# ProPrj_LED__2025-12-14-09-56-37.net
KiCad netlist of a schematic drawn in EasyEDA Pro
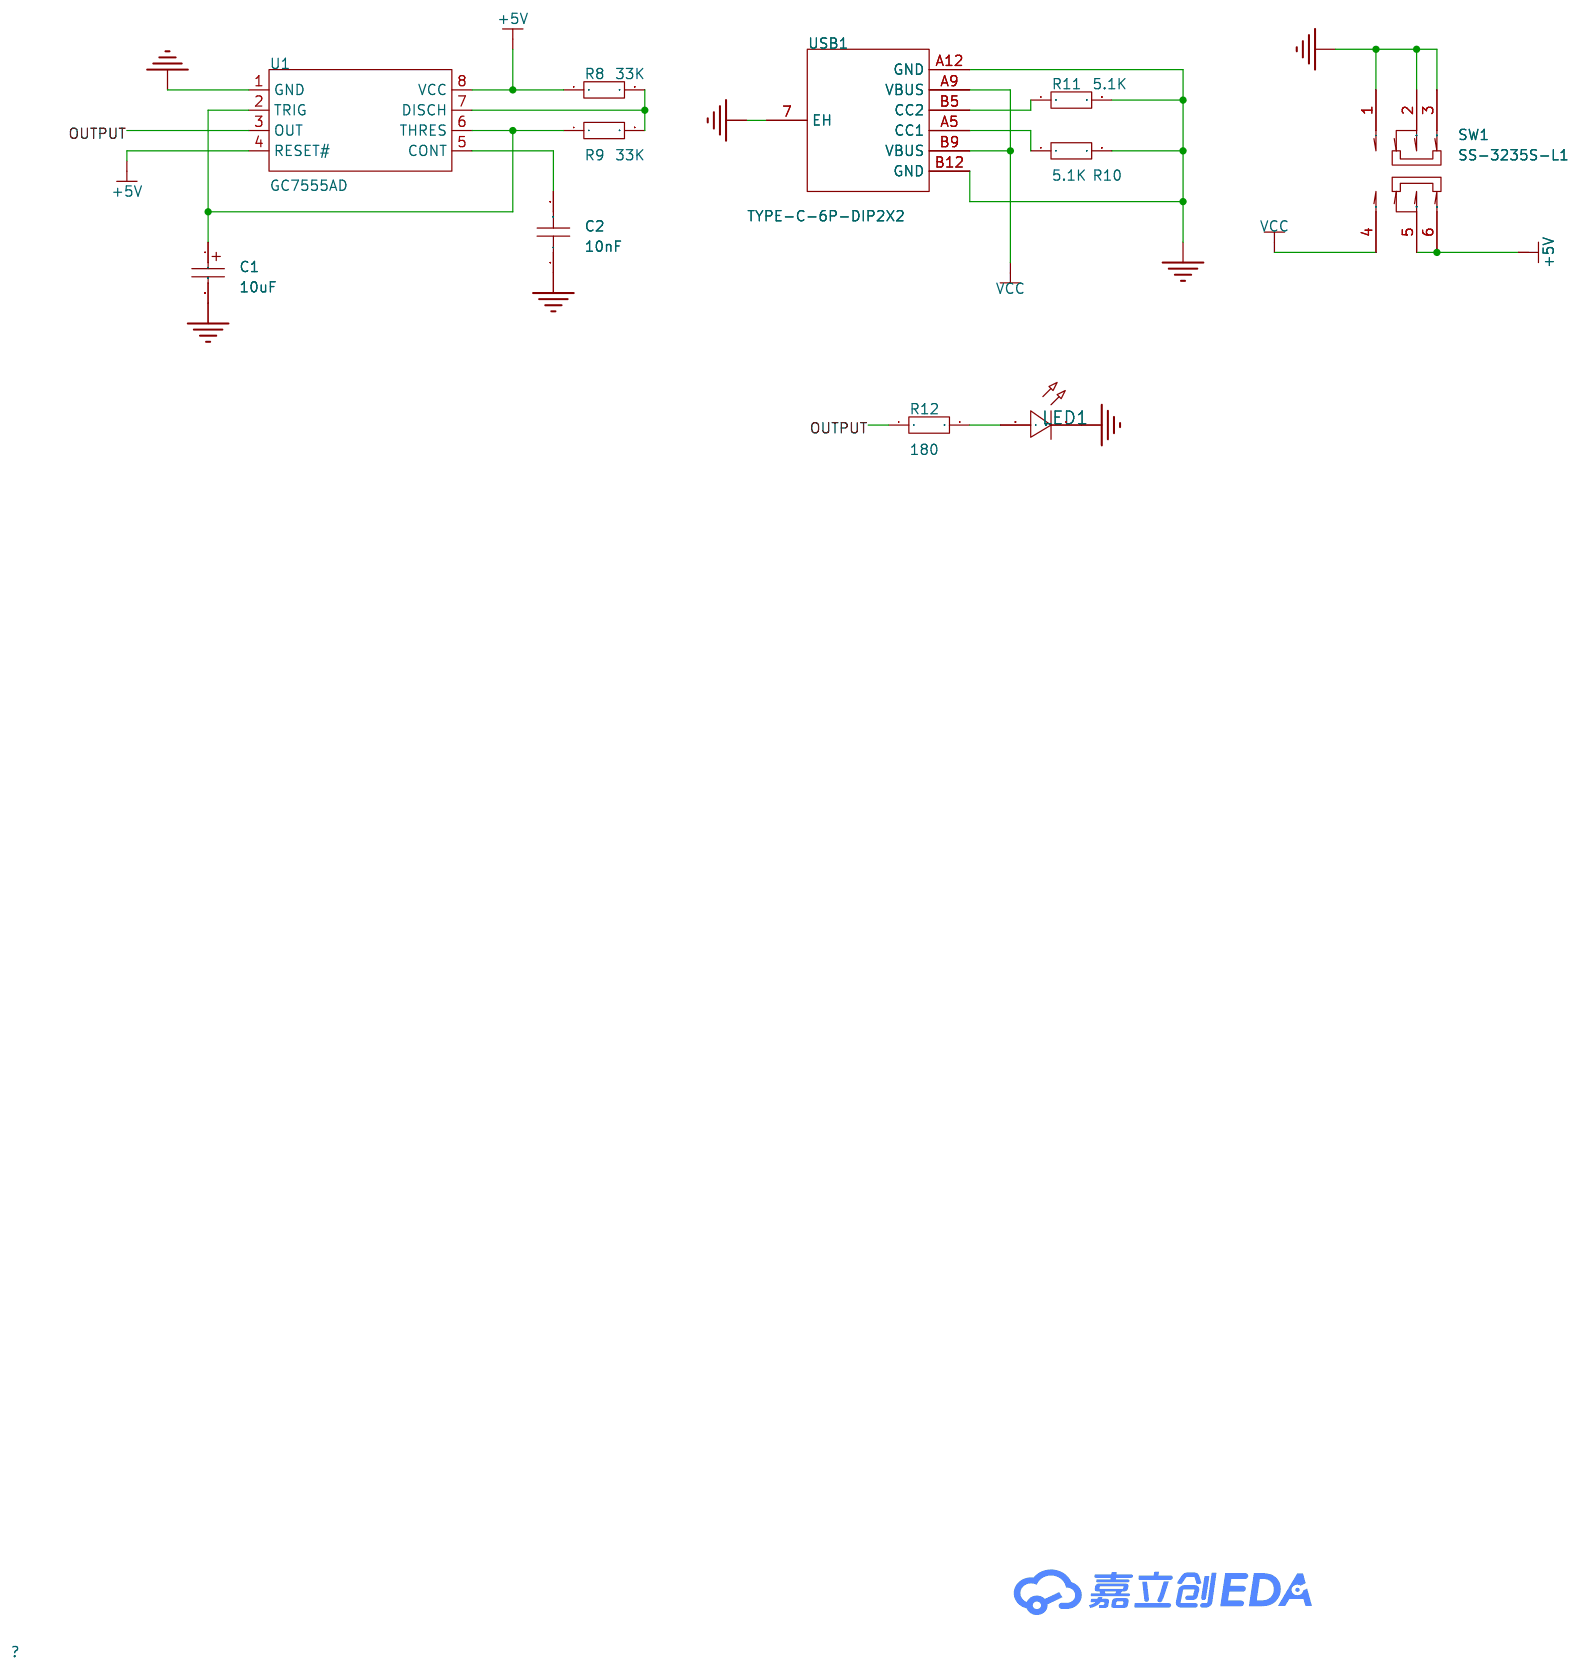
[diagram p0: schematic sheet]

(export (version "E")
  (design (tool "Eeschema 10.0.6"))
  (components
    (comp (ref "C1")
      (value "10uF")
      (footprint "easyedapro:C_Ele_SMD_3x5.4mm")
      (libsource (lib "easyedapro") (part "CAP"))
    )
    (comp (ref "C2")
      (value "10nF")
      (footprint "easyedapro:C0603")
      (libsource (lib "easyedapro") (part "Capacitance"))
    )
    (comp (ref "LED1")
      (value "~")
      (footprint "easyedapro:LED_0603")
      (libsource (lib "easyedapro") (part "LED_R"))
    )
    (comp (ref "R8") (value "33K") (footprint "easyedapro:R0805") (libsource (lib "easyedapro") (part "电阻")))
    (comp (ref "R9") (value "33K") (footprint "easyedapro:R0805") (libsource (lib "easyedapro") (part "电阻")))
    (comp (ref "R10")
      (value "5.1K")
      (footprint "easyedapro:R0805")
      (libsource (lib "easyedapro") (part "电阻"))
    )
    (comp (ref "R11")
      (value "5.1K")
      (footprint "easyedapro:R0805")
      (libsource (lib "easyedapro") (part "电阻"))
    )
    (comp (ref "R12") (value "180") (footprint "easyedapro:R0805") (libsource (lib "easyedapro") (part "电阻")))
    (comp (ref "SW1")
      (value "SS-3235S-L1")
      (footprint "easyedapro:SW-SMD_SS-3235S-LX")
      (description "电路结构:双刀双掷;安装方式:卧贴;开关颜色:黑色;额定电流:50mA;额定电压:12V;工作寿命:1万次;")
      (fields (field (name "Manufacturer") "XKB Connection(中国星坤)"))
      (libsource (lib "easyedapro") (part "SS-3235S-L1"))
    )
    (comp (ref "U1")
      (value "GC7555AD")
      (footprint "easyedapro:PDIP-8_L9.5-W6.4-P2.54-LS7.6-BL")
      (description "通用计时器：时基电路；计时；脉冲产生；满足用户（至少工业级）自主可控的需求。")
      (fields (field (name "Manufacturer") "Sungine(双竞集成)"))
      (libsource (lib "easyedapro") (part "GC7555AD"))
    )
    (comp (ref "USB1")
      (value "TYPE-C-6P-DIP2X2")
      (footprint "easyedapro:TYPE-C-SMD_TYPE-C-6P")
      (libsource (lib "easyedapro") (part "TYPE-C-6P-DIP2X2"))
    )
  )
  (nets
    (net (code "1") (name "+5V") (class "Default")
      (node (ref "R8") (pin "1") (pinfunction "1_1") (pintype "input"))
      (node (ref "SW1") (pin "5") (pinfunction "5_5") (pintype "unspecified"))
      (node (ref "SW1") (pin "6") (pinfunction "6_6") (pintype "unspecified"))
      (node (ref "U1") (pin "4") (pinfunction "RESET#_4") (pintype "unspecified"))
      (node (ref "U1") (pin "8") (pinfunction "VCC_8") (pintype "unspecified"))
    )
    (net (code "2") (name "/OUTPUT") (class "Default")
      (node (ref "R12") (pin "1") (pinfunction "1_1") (pintype "input"))
      (node (ref "U1") (pin "3") (pinfunction "OUT_3") (pintype "unspecified"))
    )
    (net (code "3") (name "GND") (class "Default")
      (node (ref "C1") (pin "2") (pinfunction "2_2") (pintype "input"))
      (node (ref "C2") (pin "1") (pinfunction "1_1") (pintype "input"))
      (node (ref "LED1") (pin "1") (pinfunction "C_1") (pintype "input"))
      (node (ref "R10") (pin "2") (pinfunction "2_2") (pintype "input"))
      (node (ref "R11") (pin "2") (pinfunction "2_2") (pintype "input"))
      (node (ref "SW1") (pin "1") (pinfunction "1_1") (pintype "unspecified"))
      (node (ref "SW1") (pin "2") (pinfunction "2_2") (pintype "unspecified"))
      (node (ref "SW1") (pin "3") (pinfunction "3_3") (pintype "unspecified"))
      (node (ref "U1") (pin "1") (pinfunction "GND_1") (pintype "unspecified"))
      (node (ref "USB1") (pin "7") (pinfunction "EH_7") (pintype "unspecified"))
      (node (ref "USB1") (pin "A12") (pinfunction "GND_A12") (pintype "unspecified"))
      (node (ref "USB1") (pin "B12") (pinfunction "GND_B12") (pintype "unspecified"))
    )
    (net (code "4") (name "Net-(LED1-A)") (class "Default")
      (node (ref "LED1") (pin "2") (pinfunction "A_2") (pintype "input"))
      (node (ref "R12") (pin "2") (pinfunction "2_2") (pintype "input"))
    )
    (net (code "5") (name "Net-(U1-CONT)") (class "Default")
      (node (ref "C2") (pin "2") (pinfunction "2_2") (pintype "input"))
      (node (ref "U1") (pin "5") (pinfunction "CONT_5") (pintype "unspecified"))
    )
    (net (code "6") (name "Net-(U1-DISCH)") (class "Default")
      (node (ref "R8") (pin "2") (pinfunction "2_2") (pintype "input"))
      (node (ref "R9") (pin "2") (pinfunction "2_2") (pintype "input"))
      (node (ref "U1") (pin "7") (pinfunction "DISCH_7") (pintype "unspecified"))
    )
    (net (code "7") (name "Net-(U1-THRES)") (class "Default")
      (node (ref "C1") (pin "1") (pinfunction "1_1") (pintype "input"))
      (node (ref "R9") (pin "1") (pinfunction "1_1") (pintype "input"))
      (node (ref "U1") (pin "2") (pinfunction "TRIG_2") (pintype "unspecified"))
      (node (ref "U1") (pin "6") (pinfunction "THRES_6") (pintype "unspecified"))
    )
    (net (code "8") (name "Net-(USB1-CC1)") (class "Default")
      (node (ref "R10") (pin "1") (pinfunction "1_1") (pintype "input"))
      (node (ref "USB1") (pin "A5") (pinfunction "CC1_A5") (pintype "unspecified"))
    )
    (net (code "9") (name "Net-(USB1-CC2)") (class "Default")
      (node (ref "R11") (pin "1") (pinfunction "1_1") (pintype "input"))
      (node (ref "USB1") (pin "B5") (pinfunction "CC2_B5") (pintype "unspecified"))
    )
    (net (code "10") (name "VCC") (class "Default")
      (node (ref "SW1") (pin "4") (pinfunction "4_4") (pintype "unspecified"))
      (node (ref "USB1") (pin "A9") (pinfunction "VBUS_A9") (pintype "unspecified"))
      (node (ref "USB1") (pin "B9") (pinfunction "VBUS_B9") (pintype "unspecified"))
    )
  )
)
